# microNrf.net
KiCad netlist of a schematic drawn in EAGLE
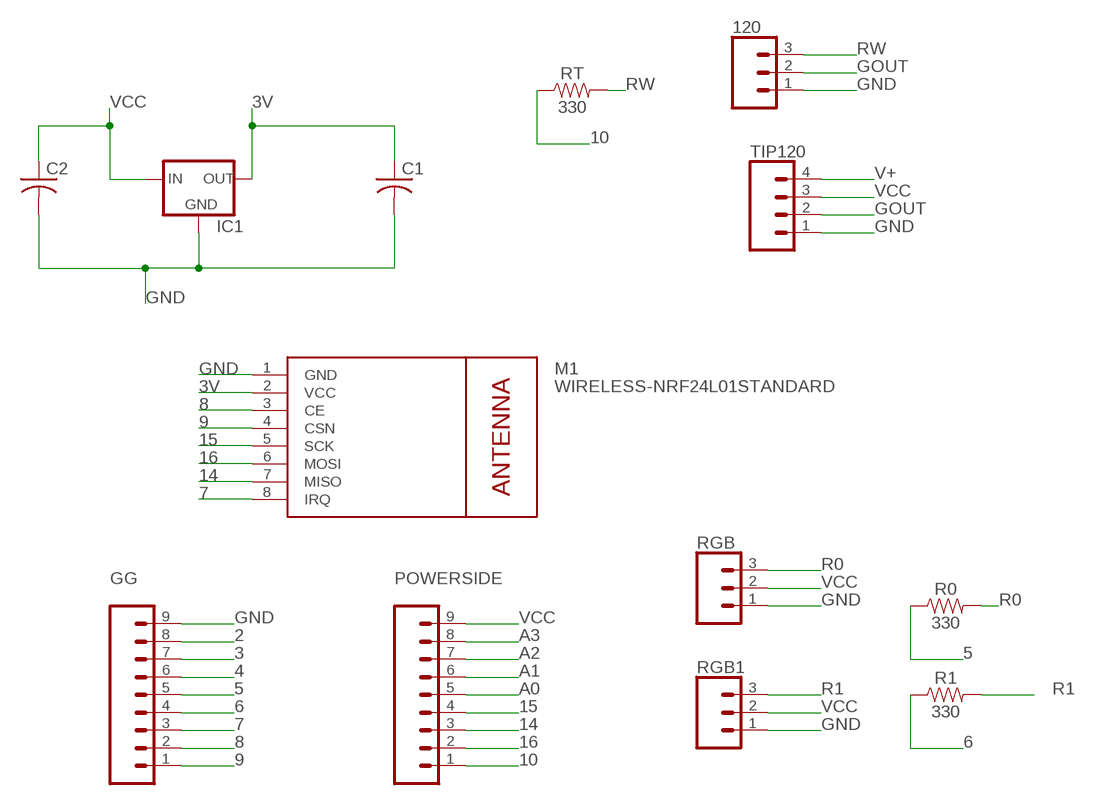
[diagram p0: schematic, sheet 1]

(export (version "E")
  (design (tool "Eeschema 10.0.6"))
  (components
    (comp (ref "120")
      (value "CONN_03LONGPADS")
      (footprint "eagle-import:1X03_LONGPADS")
      (libsource (lib "eagle-import") (part "CONN_03LONGPADS"))
    )
    (comp (ref "C1")
      (value "C-US025-030X050")
      (footprint "eagle-import:C025-030X050")
      (libsource (lib "eagle-import") (part "C-US025-030X050"))
    )
    (comp (ref "C2")
      (value "C-US025-030X050")
      (footprint "eagle-import:C025-030X050")
      (libsource (lib "eagle-import") (part "C-US025-030X050"))
    )
    (comp (ref "GG")
      (value "CONN_09")
      (footprint "eagle-import:1X09")
      (libsource (lib "eagle-import") (part "CONN_09"))
    )
    (comp (ref "IC1")
      (value "MCP1700TRI")
      (footprint "eagle-import:TO92")
      (libsource (lib "eagle-import") (part "MCP1700TRI"))
    )
    (comp (ref "M1")
      (value "WIRELESS-NRF24L01STANDARD")
      (footprint "eagle-import:WIRELESS-NRF24L01")
      (libsource (lib "eagle-import") (part "WIRELESS-NRF24L01STANDARD"))
    )
    (comp (ref "POWERSIDE")
      (value "CONN_09")
      (footprint "eagle-import:1X09")
      (libsource (lib "eagle-import") (part "CONN_09"))
    )
    (comp (ref "R0")
      (value "330")
      (footprint "eagle-import:0603")
      (libsource (lib "eagle-import") (part "330OHM-0603-1/10W-1%"))
    )
    (comp (ref "R1")
      (value "330")
      (footprint "eagle-import:0603")
      (libsource (lib "eagle-import") (part "330OHM-0603-1/10W-1%"))
    )
    (comp (ref "RGB")
      (value "CONN_03LONGPADS")
      (footprint "eagle-import:1X03_LONGPADS")
      (libsource (lib "eagle-import") (part "CONN_03LONGPADS"))
    )
    (comp (ref "RGB1")
      (value "CONN_03LONGPADS")
      (footprint "eagle-import:1X03_LONGPADS")
      (libsource (lib "eagle-import") (part "CONN_03LONGPADS"))
    )
    (comp (ref "RT")
      (value "330")
      (footprint "eagle-import:0603")
      (libsource (lib "eagle-import") (part "330OHM-0603-1/10W-1%"))
    )
    (comp (ref "TIP120")
      (value "CONN_04LONGPADS")
      (footprint "eagle-import:1X04_LONGPADS")
      (libsource (lib "eagle-import") (part "CONN_04LONGPADS"))
    )
  )
  (nets
    (net (code "1") (name "/2") (class "Default")
      (node (ref "GG") (pin "8") (pinfunction "8_8") (pintype "passive"))
    )
    (net (code "2") (name "/3") (class "Default")
      (node (ref "GG") (pin "7") (pinfunction "7_7") (pintype "passive"))
    )
    (net (code "3") (name "/3V") (class "Default")
      (node (ref "C1") (pin "1") (pinfunction "1_1") (pintype "passive"))
      (node (ref "IC1") (pin "3") (pinfunction "OUT_3") (pintype "passive"))
      (node (ref "M1") (pin "2") (pinfunction "VCC_2") (pintype "power_in"))
    )
    (net (code "4") (name "/4") (class "Default")
      (node (ref "GG") (pin "6") (pinfunction "6_6") (pintype "passive"))
    )
    (net (code "5") (name "/5") (class "Default")
      (node (ref "GG") (pin "5") (pinfunction "5_5") (pintype "passive"))
      (node (ref "R0") (pin "1") (pinfunction "1_1") (pintype "passive"))
    )
    (net (code "6") (name "/6") (class "Default")
      (node (ref "GG") (pin "4") (pinfunction "4_4") (pintype "passive"))
      (node (ref "R1") (pin "1") (pinfunction "1_1") (pintype "passive"))
    )
    (net (code "7") (name "/7") (class "Default")
      (node (ref "GG") (pin "3") (pinfunction "3_3") (pintype "passive"))
      (node (ref "M1") (pin "8") (pinfunction "IRQ_8") (pintype "bidirectional"))
    )
    (net (code "8") (name "/8") (class "Default")
      (node (ref "GG") (pin "2") (pinfunction "2_2") (pintype "passive"))
      (node (ref "M1") (pin "3") (pinfunction "CE_3") (pintype "bidirectional"))
    )
    (net (code "9") (name "/9") (class "Default")
      (node (ref "GG") (pin "1") (pinfunction "1_1") (pintype "passive"))
      (node (ref "M1") (pin "4") (pinfunction "CSN_4") (pintype "bidirectional"))
    )
    (net (code "10") (name "/10") (class "Default")
      (node (ref "POWERSIDE") (pin "1") (pinfunction "1_1") (pintype "passive"))
      (node (ref "RT") (pin "1") (pinfunction "1_1") (pintype "passive"))
    )
    (net (code "11") (name "/14") (class "Default")
      (node (ref "M1") (pin "7") (pinfunction "MISO_7") (pintype "bidirectional"))
      (node (ref "POWERSIDE") (pin "3") (pinfunction "3_3") (pintype "passive"))
    )
    (net (code "12") (name "/15") (class "Default")
      (node (ref "M1") (pin "5") (pinfunction "SCK_5") (pintype "bidirectional"))
      (node (ref "POWERSIDE") (pin "4") (pinfunction "4_4") (pintype "passive"))
    )
    (net (code "13") (name "/16") (class "Default")
      (node (ref "M1") (pin "6") (pinfunction "MOSI_6") (pintype "bidirectional"))
      (node (ref "POWERSIDE") (pin "2") (pinfunction "2_2") (pintype "passive"))
    )
    (net (code "14") (name "/A0") (class "Default")
      (node (ref "POWERSIDE") (pin "5") (pinfunction "5_5") (pintype "passive"))
    )
    (net (code "15") (name "/A1") (class "Default")
      (node (ref "POWERSIDE") (pin "6") (pinfunction "6_6") (pintype "passive"))
    )
    (net (code "16") (name "/A2") (class "Default")
      (node (ref "POWERSIDE") (pin "7") (pinfunction "7_7") (pintype "passive"))
    )
    (net (code "17") (name "/A3") (class "Default")
      (node (ref "POWERSIDE") (pin "8") (pinfunction "8_8") (pintype "passive"))
    )
    (net (code "18") (name "/GND") (class "Default")
      (node (ref "120") (pin "1") (pinfunction "1_1") (pintype "passive"))
      (node (ref "C1") (pin "2") (pinfunction "2_2") (pintype "passive"))
      (node (ref "C2") (pin "2") (pinfunction "2_2") (pintype "passive"))
      (node (ref "GG") (pin "9") (pinfunction "9_9") (pintype "passive"))
      (node (ref "IC1") (pin "1") (pinfunction "GND_1") (pintype "input"))
      (node (ref "M1") (pin "1") (pinfunction "GND_1") (pintype "power_in"))
      (node (ref "RGB") (pin "1") (pinfunction "1_1") (pintype "passive"))
      (node (ref "RGB1") (pin "1") (pinfunction "1_1") (pintype "passive"))
      (node (ref "TIP120") (pin "1") (pinfunction "1_1") (pintype "passive"))
    )
    (net (code "19") (name "/GOUT") (class "Default")
      (node (ref "120") (pin "2") (pinfunction "2_2") (pintype "passive"))
      (node (ref "TIP120") (pin "2") (pinfunction "2_2") (pintype "passive"))
    )
    (net (code "20") (name "/R0") (class "Default")
      (node (ref "R0") (pin "2") (pinfunction "2_2") (pintype "passive"))
      (node (ref "RGB") (pin "3") (pinfunction "3_3") (pintype "passive"))
    )
    (net (code "21") (name "/R1") (class "Default")
      (node (ref "R1") (pin "2") (pinfunction "2_2") (pintype "passive"))
      (node (ref "RGB1") (pin "3") (pinfunction "3_3") (pintype "passive"))
    )
    (net (code "22") (name "/RW") (class "Default")
      (node (ref "120") (pin "3") (pinfunction "3_3") (pintype "passive"))
      (node (ref "RT") (pin "2") (pinfunction "2_2") (pintype "passive"))
    )
    (net (code "23") (name "/V+") (class "Default")
      (node (ref "TIP120") (pin "4") (pinfunction "4_4") (pintype "passive"))
    )
    (net (code "24") (name "/VCC") (class "Default")
      (node (ref "C2") (pin "1") (pinfunction "1_1") (pintype "passive"))
      (node (ref "IC1") (pin "2") (pinfunction "IN_2") (pintype "input"))
      (node (ref "POWERSIDE") (pin "9") (pinfunction "9_9") (pintype "passive"))
      (node (ref "RGB") (pin "2") (pinfunction "2_2") (pintype "passive"))
      (node (ref "RGB1") (pin "2") (pinfunction "2_2") (pintype "passive"))
      (node (ref "TIP120") (pin "3") (pinfunction "3_3") (pintype "passive"))
    )
  )
)
